# MCED_schematic.net
KiCad netlist of a schematic drawn in Altium Designer
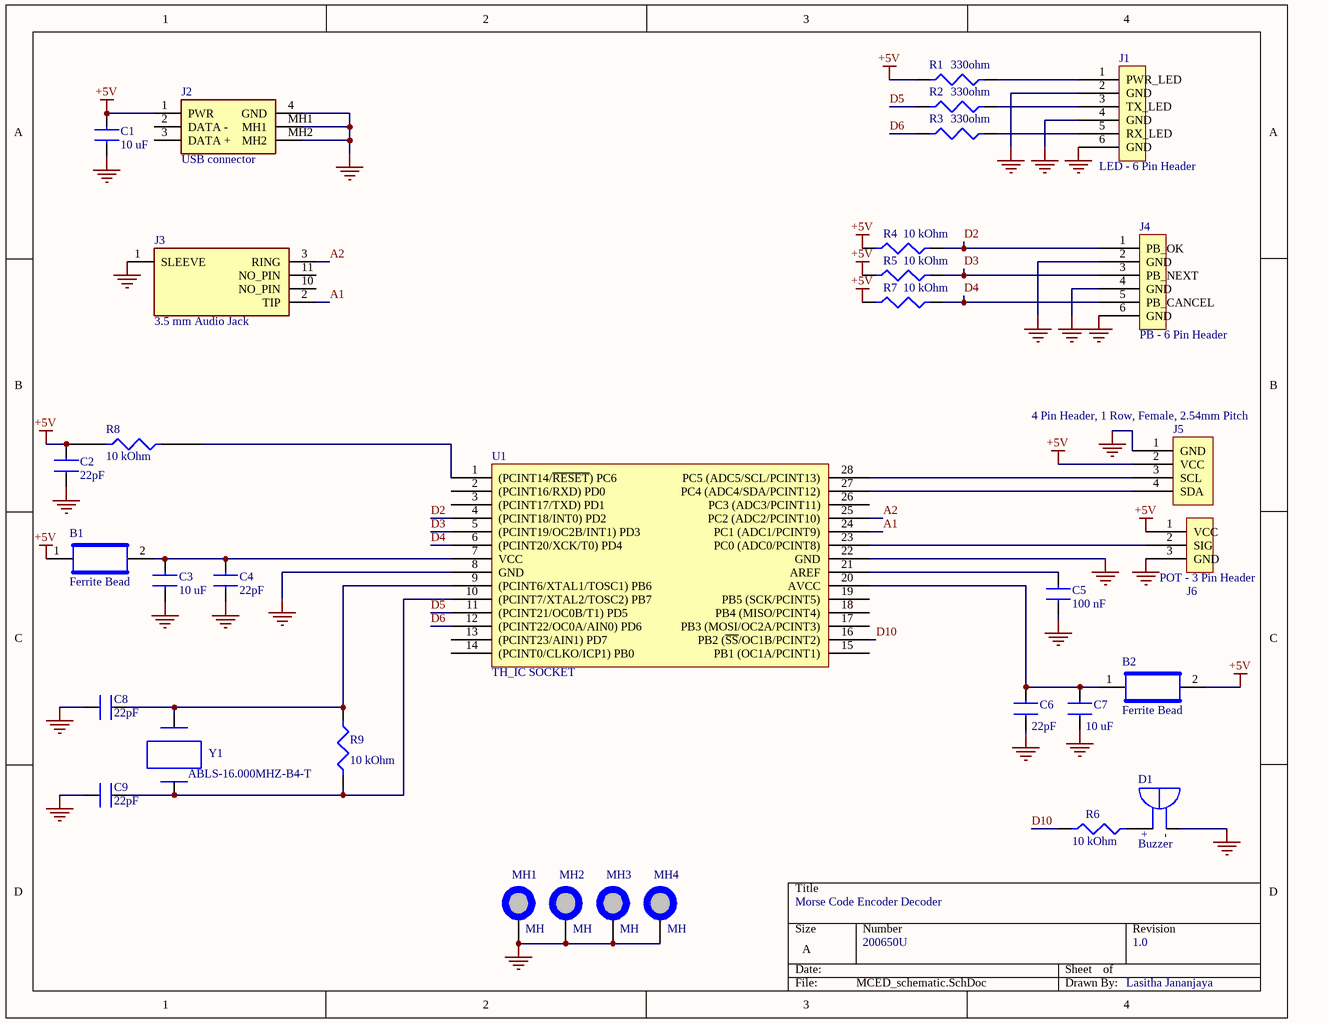
[diagram p0: MCED_schematic.SchDoc]

(export (version "E")
  (design (tool "Eeschema 10.0.6"))
  (components
    (comp (ref "B1")
      (value "Ferrite Bead")
      (footprint "FERRITE BEAD C2012X105N")
      (description "Ferrite Bead, 1 Function(s), 2A")
      (fields
        (field (name "MANUFACTURER") "TDK")
        (field (name "MANUFACTURER PART NUMBER") "MPZ2012S601AT000")
      )
      (libsource (lib "MCED_Schlib") (part "MPZ2012S601AT000"))
    )
    (comp (ref "B2")
      (value "Ferrite Bead")
      (footprint "FERRITE BEAD C2012X105N")
      (description "Ferrite Bead, 1 Function(s), 2A")
      (fields
        (field (name "MANUFACTURER") "TDK")
        (field (name "MANUFACTURER PART NUMBER") "MPZ2012S601AT000")
      )
      (libsource (lib "MCED_Schlib") (part "MPZ2012S601AT000"))
    )
    (comp (ref "C1")
      (value "10 uF")
      (footprint "C0805")
      (fields
        (field (name "MANUFACTURER") "Samsung")
        (field (name "MANUFACTURER PART NUMBER") "CL21A106KBYQNNE")
      )
      (libsource (lib "MCED_Schlib") (part "CL21A106KBYQNNE"))
    )
    (comp (ref "C2")
      (value "22pF")
      (footprint "C0805")
      (fields
        (field (name "MANUFACTURER") "Vishay Vitramon")
        (field (name "MANUFACTURER PART NUMBER") "VJ0805A220GXACW1BC")
      )
      (libsource (lib "MCED_Schlib") (part "VJ0805A220GXACW1BC"))
    )
    (comp (ref "C3")
      (value "10 uF")
      (footprint "C0805")
      (fields
        (field (name "MANUFACTURER") "Samsung")
        (field (name "MANUFACTURER PART NUMBER") "CL21A106KBYQNNE")
      )
      (libsource (lib "MCED_Schlib") (part "CL21A106KBYQNNE"))
    )
    (comp (ref "C4")
      (value "22pF")
      (footprint "C0805")
      (fields
        (field (name "MANUFACTURER") "Vishay Vitramon")
        (field (name "MANUFACTURER PART NUMBER") "VJ0805A220GXACW1BC")
      )
      (libsource (lib "MCED_Schlib") (part "VJ0805A220GXACW1BC"))
    )
    (comp (ref "C5")
      (value "100 nF")
      (footprint "C0805")
      (fields
        (field (name "MANUFACTURER") "Samsung")
        (field (name "MANUFACTURER PART NUMBER") "CL21A106KBYQNNE")
      )
      (libsource (lib "MCED_Schlib") (part "CL21A106KBYQNNE"))
    )
    (comp (ref "C6")
      (value "22pF")
      (footprint "C0805")
      (fields
        (field (name "MANUFACTURER") "Vishay Vitramon")
        (field (name "MANUFACTURER PART NUMBER") "VJ0805A220GXACW1BC")
      )
      (libsource (lib "MCED_Schlib") (part "VJ0805A220GXACW1BC"))
    )
    (comp (ref "C7")
      (value "10 uF")
      (footprint "C0805")
      (fields
        (field (name "MANUFACTURER") "Samsung")
        (field (name "MANUFACTURER PART NUMBER") "CL21A106KBYQNNE")
      )
      (libsource (lib "MCED_Schlib") (part "CL21A106KBYQNNE"))
    )
    (comp (ref "C8")
      (value "22pF")
      (footprint "C0805")
      (fields
        (field (name "MANUFACTURER") "Vishay Vitramon")
        (field (name "MANUFACTURER PART NUMBER") "VJ0805A220GXACW1BC")
      )
      (libsource (lib "MCED_Schlib") (part "VJ0805A220GXACW1BC"))
    )
    (comp (ref "C9")
      (value "22pF")
      (footprint "C0805")
      (fields
        (field (name "MANUFACTURER") "Vishay Vitramon")
        (field (name "MANUFACTURER PART NUMBER") "VJ0805A220GXACW1BC")
      )
      (libsource (lib "MCED_Schlib") (part "VJ0805A220GXACW1BC"))
    )
    (comp (ref "D1")
      (value "Buzzer")
      (footprint "Buzzer")
      (fields (field (name "MF") "Kingstate") (field (name "MP") "KXG1201C"))
      (libsource (lib "MCED_Schlib") (part "KXG1201C"))
    )
    (comp (ref "J1")
      (value "LED - 6 Pin Header")
      (footprint "6 PIN HEADER")
      (description "6 Pin Header Board Connector")
      (fields (field (name "MANUFACTURER") "3M") (field (name "MANUFACTURER PART NUMBER") "929850-01-06-RB"))
      (libsource (lib "MCED_Schlib") (part "929850-01-06-RB"))
    )
    (comp (ref "J2")
      (value "USB connector")
      (footprint "USB 2.0 type B 617291011BLF")
      (description "USB 2.0 connector, Type B, Receptacle, Through Hole, 30u GXT Contact, 4 Pins, 1.57mm PCB")
      (fields
        (field (name "MANUFACTURER") "Amphenol ICC / FCI")
        (field (name "MANUFACTURER PART NUMBER") "61729-1011BLF")
      )
      (libsource (lib "MCED_Schlib") (part "61729-1011BLF"))
    )
    (comp (ref "J3")
      (value "3.5 mm Audio Jack")
      (footprint "Audio Jack SJ13523N")
      (description "3.5 mm Audio Jack, Female, 3 Pole(s), Solder Terminal, Jack")
      (fields
        (field (name "MANUFACTURER") "CUI Devices")
        (field (name "MANUFACTURER PART NUMBER") "SJ1-3523N")
      )
      (libsource (lib "MCED_Schlib") (part "SJ1-3523N"))
    )
    (comp (ref "J4")
      (value "PB - 6 Pin Header")
      (footprint "6 PIN HEADER")
      (description "6 Pin Header Board Connector")
      (fields (field (name "MANUFACTURER") "3M") (field (name "MANUFACTURER PART NUMBER") "929850-01-06-RB"))
      (libsource (lib "MCED_Schlib") (part "929850-01-06-RB"))
    )
    (comp (ref "J5")
      (value "4 Pin Header, 1 Row, Female, 2.54mm Pitch")
      (footprint "4 Pin Header")
      (fields (field (name "MANUFACTURER") "Harwin") (field (name "MANUFACTURER PART NUMBER") "M20-7820446"))
      (libsource (lib "MCED_Schlib") (part "M20-7820446"))
    )
    (comp (ref "J6")
      (value "POT - 3 Pin Header")
      (footprint "3 PIN HEADER")
      (description "3 Pin Header Board Connector, 3 Contact(s), 1 Row(s), Female, Straight, Solder Terminal, Socket")
      (fields (field (name "MANUFACTURER") "3M") (field (name "MANUFACTURER PART NUMBER") "929850-01-03-RA"))
      (libsource (lib "MCED_Schlib") (part "929850-01-03-RA"))
    )
    (comp (ref "MH1")
      (value "MH")
      (footprint "Mounting Hole")
      (libsource (lib "MCED_Schlib") (part "Mounting Hole"))
    )
    (comp (ref "MH2")
      (value "MH")
      (footprint "Mounting Hole")
      (libsource (lib "MCED_Schlib") (part "Mounting Hole"))
    )
    (comp (ref "MH3")
      (value "MH")
      (footprint "Mounting Hole")
      (libsource (lib "MCED_Schlib") (part "Mounting Hole"))
    )
    (comp (ref "MH4")
      (value "MH")
      (footprint "Mounting Hole")
      (libsource (lib "MCED_Schlib") (part "Mounting Hole"))
    )
    (comp (ref "R1")
      (value "330ohm")
      (footprint "300Ohm RESC2012X60N")
      (fields
        (field (name "MANUFACTURER") "Vishay")
        (field (name "MANUFACTURER PART NUMBER") "CRCW0805330RFKEA")
        (field (name "TOLERANCE") "1%")
      )
      (libsource (lib "MCED_Schlib") (part "CRCW0805330RFKEA"))
    )
    (comp (ref "R2")
      (value "330ohm")
      (footprint "300Ohm RESC2012X60N")
      (fields
        (field (name "MANUFACTURER") "Vishay")
        (field (name "MANUFACTURER PART NUMBER") "CRCW0805330RFKEA")
        (field (name "TOLERANCE") "1%")
      )
      (libsource (lib "MCED_Schlib") (part "CRCW0805330RFKEA"))
    )
    (comp (ref "R3")
      (value "330ohm")
      (footprint "300Ohm RESC2012X60N")
      (fields
        (field (name "MANUFACTURER") "Vishay")
        (field (name "MANUFACTURER PART NUMBER") "CRCW0805330RFKEA")
        (field (name "TOLERANCE") "1%")
      )
      (libsource (lib "MCED_Schlib") (part "CRCW0805330RFKEA"))
    )
    (comp (ref "R4")
      (value "10 kOhm")
      (footprint "10K")
      (description "10 kOhm, Fixed Resistor, Thin Film, 0.2W, 10000ohm, 150V, 0.5% +/-Tol, -25,25ppm/Cel, 0805")
      (fields
        (field (name "MANUFACTURER") "Vishay Beyschlag")
        (field (name "MANUFACTURER PART NUMBER") "MCU0805MD1002DP500")
      )
      (libsource (lib "MCED_Schlib") (part "MCU0805MD1002DP500"))
    )
    (comp (ref "R5")
      (value "10 kOhm")
      (footprint "10K")
      (description "10 kOhm, Fixed Resistor, Thin Film, 0.2W, 10000ohm, 150V, 0.5% +/-Tol, -25,25ppm/Cel, 0805")
      (fields
        (field (name "MANUFACTURER") "Vishay Beyschlag")
        (field (name "MANUFACTURER PART NUMBER") "MCU0805MD1002DP500")
      )
      (libsource (lib "MCED_Schlib") (part "MCU0805MD1002DP500"))
    )
    (comp (ref "R6")
      (value "10 kOhm")
      (footprint "10K")
      (description "10 kOhm, Fixed Resistor, Thin Film, 0.2W, 10000ohm, 150V, 0.5% +/-Tol, -25,25ppm/Cel, 0805")
      (fields
        (field (name "MANUFACTURER") "Vishay Beyschlag")
        (field (name "MANUFACTURER PART NUMBER") "MCU0805MD1002DP500")
      )
      (libsource (lib "MCED_Schlib") (part "MCU0805MD1002DP500"))
    )
    (comp (ref "R7")
      (value "10 kOhm")
      (footprint "10K")
      (description "10 kOhm, Fixed Resistor, Thin Film, 0.2W, 10000ohm, 150V, 0.5% +/-Tol, -25,25ppm/Cel, 0805")
      (fields
        (field (name "MANUFACTURER") "Vishay Beyschlag")
        (field (name "MANUFACTURER PART NUMBER") "MCU0805MD1002DP500")
      )
      (libsource (lib "MCED_Schlib") (part "MCU0805MD1002DP500"))
    )
    (comp (ref "R8")
      (value "10 kOhm")
      (footprint "10K")
      (description "10 kOhm, Fixed Resistor, Thin Film, 0.2W, 10000ohm, 150V, 0.5% +/-Tol, -25,25ppm/Cel, 0805")
      (fields
        (field (name "MANUFACTURER") "Vishay Beyschlag")
        (field (name "MANUFACTURER PART NUMBER") "MCU0805MD1002DP500")
      )
      (libsource (lib "") (part "MCU0805MD1002DP500_1"))
    )
    (comp (ref "R9")
      (value "10 kOhm")
      (footprint "10K")
      (description "10 kOhm, Fixed Resistor, Thin Film, 0.2W, 10000ohm, 150V, 0.5% +/-Tol, -25,25ppm/Cel, 0805")
      (fields
        (field (name "MANUFACTURER") "Vishay Beyschlag")
        (field (name "MANUFACTURER PART NUMBER") "MCU0805MD1002DP500")
      )
      (libsource (lib "MCED_Schlib") (part "MCU0805MD1002DP500"))
    )
    (comp (ref "U1")
      (value "TH_IC SOCKET")
      (footprint "28dip_through_hole_ic_socket")
      (description "Through Hole IC Sockets 28P / .300\"")
      (fields
        (field (name "MANUFACTURER") "Adam Equipment")
        (field (name "MANUFACTURER PART NUMBER") "ICS-328-T")
      )
      (libsource (lib "MCED_Schlib") (part "ICS-328-T"))
    )
    (comp (ref "Y1")
      (value "ABLS-16.000MHZ-B4-T")
      (footprint "ABLS-16.000MHZ-B4-T_CRYSTAL")
      (description "16MHz ±30ppm 晶体 18pF 40 欧姆 -20°C ~ 70°C  表面贴装 HC49/US")
      (fields (field (name "MANUFACTURER") "Abracon"))
      (libsource (lib "MCED_Schlib") (part "ABLS-16.000MHZ-B4-T"))
    )
  )
  (nets
    (net (code "1") (name "+5V") (class "Default")
      (node (ref "B1") (pin "1") (pinfunction "1_1") (pintype "passive"))
      (node (ref "B2") (pin "2") (pinfunction "2_2") (pintype "passive"))
      (node (ref "C1") (pin "2") (pinfunction "2_2") (pintype "passive"))
      (node (ref "C2") (pin "2") (pinfunction "2_2") (pintype "passive"))
      (node (ref "J2") (pin "1") (pinfunction "PWR_1") (pintype "passive"))
      (node (ref "J5") (pin "2") (pinfunction "VCC_2") (pintype "passive"))
      (node (ref "J6") (pin "1") (pinfunction "VCC_1") (pintype "passive"))
      (node (ref "R1") (pin "1") (pinfunction "1_1") (pintype "passive"))
      (node (ref "R4") (pin "2") (pinfunction "2_2") (pintype "passive"))
      (node (ref "R5") (pin "2") (pinfunction "2_2") (pintype "passive"))
      (node (ref "R7") (pin "2") (pinfunction "2_2") (pintype "passive"))
      (node (ref "R8") (pin "2") (pinfunction "2_2") (pintype "passive"))
    )
    (net (code "2") (name "/A1") (class "Default")
      (node (ref "J3") (pin "2") (pinfunction "TIP_2") (pintype "passive"))
      (node (ref "U1") (pin "24") (pinfunction "PC1_(ADC1/PCINT9)_24") (pintype "passive"))
    )
    (net (code "3") (name "/A2") (class "Default")
      (node (ref "J3") (pin "3") (pinfunction "RING_3") (pintype "passive"))
      (node (ref "U1") (pin "25") (pinfunction "PC2_(ADC2/PCINT10)_25") (pintype "passive"))
    )
    (net (code "4") (name "/D2") (class "Default")
      (node (ref "J4") (pin "1") (pinfunction "PWR_LED_1") (pintype "passive"))
      (node (ref "R4") (pin "1") (pinfunction "1_1") (pintype "passive"))
      (node (ref "U1") (pin "4") (pinfunction "(PCINT18/INT0)_PD2_4") (pintype "passive"))
    )
    (net (code "5") (name "/D3") (class "Default")
      (node (ref "J4") (pin "3") (pinfunction "TX_LED_3") (pintype "passive"))
      (node (ref "R5") (pin "1") (pinfunction "1_1") (pintype "passive"))
      (node (ref "U1") (pin "5") (pinfunction "(PCINT19/OC2B/INT1)_PD3_5") (pintype "passive"))
    )
    (net (code "6") (name "/D4") (class "Default")
      (node (ref "J4") (pin "5") (pinfunction "RX_LED_5") (pintype "passive"))
      (node (ref "R7") (pin "1") (pinfunction "1_1") (pintype "passive"))
      (node (ref "U1") (pin "6") (pinfunction "(PCINT20/XCK/T0)_PD4_6") (pintype "passive"))
    )
    (net (code "7") (name "/D5") (class "Default")
      (node (ref "R2") (pin "1") (pinfunction "1_1") (pintype "passive"))
      (node (ref "U1") (pin "11") (pinfunction "(PCINT21/OC0B/T1)_PD5_11") (pintype "passive"))
    )
    (net (code "8") (name "/D6") (class "Default")
      (node (ref "R3") (pin "1") (pinfunction "1_1") (pintype "passive"))
      (node (ref "U1") (pin "12") (pinfunction "(PCINT22/OC0A/AIN0)_PD6_12") (pintype "passive"))
    )
    (net (code "9") (name "/D10") (class "Default")
      (node (ref "R6") (pin "2") (pinfunction "2_2") (pintype "passive"))
      (node (ref "U1") (pin "16") (pinfunction "PB2_(~{SS}/OC1B/PCINT2)_16") (pintype "passive"))
    )
    (net (code "10") (name "GND") (class "Default")
      (node (ref "C1") (pin "1") (pinfunction "1_1") (pintype "passive"))
      (node (ref "C2") (pin "1") (pinfunction "1_1") (pintype "passive"))
      (node (ref "C3") (pin "1") (pinfunction "1_1") (pintype "passive"))
      (node (ref "C4") (pin "1") (pinfunction "1_1") (pintype "passive"))
      (node (ref "C5") (pin "1") (pinfunction "1_1") (pintype "passive"))
      (node (ref "C6") (pin "1") (pinfunction "1_1") (pintype "passive"))
      (node (ref "C7") (pin "1") (pinfunction "1_1") (pintype "passive"))
      (node (ref "C8") (pin "2") (pinfunction "2_2") (pintype "passive"))
      (node (ref "C9") (pin "2") (pinfunction "2_2") (pintype "passive"))
      (node (ref "D1") (pin "N") (pinfunction "NEG_N") (pintype "passive"))
      (node (ref "J1") (pin "2") (pinfunction "GND_2") (pintype "passive"))
      (node (ref "J1") (pin "4") (pinfunction "GND_4") (pintype "passive"))
      (node (ref "J1") (pin "6") (pinfunction "GND_6") (pintype "passive"))
      (node (ref "J2") (pin "4") (pinfunction "GND_4") (pintype "passive"))
      (node (ref "J2") (pin "MH1") (pinfunction "MH1_MH1") (pintype "passive"))
      (node (ref "J2") (pin "MH2") (pinfunction "MH2_MH2") (pintype "passive"))
      (node (ref "J3") (pin "1") (pinfunction "SLEEVE_1") (pintype "passive"))
      (node (ref "J4") (pin "2") (pinfunction "GND_2") (pintype "passive"))
      (node (ref "J4") (pin "4") (pinfunction "GND_4") (pintype "passive"))
      (node (ref "J4") (pin "6") (pinfunction "GND_6") (pintype "passive"))
      (node (ref "J5") (pin "1") (pinfunction "GND_1") (pintype "passive"))
      (node (ref "J6") (pin "3") (pinfunction "GND_3") (pintype "passive"))
      (node (ref "MH1") (pin "1") (pinfunction "1_1") (pintype "passive"))
      (node (ref "MH2") (pin "1") (pinfunction "1_1") (pintype "passive"))
      (node (ref "MH3") (pin "1") (pinfunction "1_1") (pintype "passive"))
      (node (ref "MH4") (pin "1") (pinfunction "1_1") (pintype "passive"))
      (node (ref "U1") (pin "22") (pinfunction "GND_22") (pintype "passive"))
      (node (ref "U1") (pin "8") (pinfunction "GND_8") (pintype "passive"))
    )
    (net (code "11") (name "Net-(D1-POS)") (class "Default")
      (node (ref "D1") (pin "P") (pinfunction "POS_P") (pintype "passive"))
      (node (ref "R6") (pin "1") (pinfunction "1_1") (pintype "passive"))
    )
    (net (code "12") (name "Net-(J1-PWR_LED)") (class "Default")
      (node (ref "J1") (pin "1") (pinfunction "PWR_LED_1") (pintype "passive"))
      (node (ref "R1") (pin "2") (pinfunction "2_2") (pintype "passive"))
    )
    (net (code "13") (name "Net-(J1-RX_LED)") (class "Default")
      (node (ref "J1") (pin "5") (pinfunction "RX_LED_5") (pintype "passive"))
      (node (ref "R3") (pin "2") (pinfunction "2_2") (pintype "passive"))
    )
    (net (code "14") (name "Net-(J1-TX_LED)") (class "Default")
      (node (ref "J1") (pin "3") (pinfunction "TX_LED_3") (pintype "passive"))
      (node (ref "R2") (pin "2") (pinfunction "2_2") (pintype "passive"))
    )
    (net (code "15") (name "Net-(J5-SCL)") (class "Default")
      (node (ref "J5") (pin "3") (pinfunction "SCL_3") (pintype "passive"))
      (node (ref "U1") (pin "28") (pinfunction "PC5_(ADC5/SCL/PCINT13)_28") (pintype "passive"))
    )
    (net (code "16") (name "Net-(J5-SDA)") (class "Default")
      (node (ref "J5") (pin "4") (pinfunction "SDA_4") (pintype "passive"))
      (node (ref "U1") (pin "27") (pinfunction "PC4_(ADC4/SDA/PCINT12)_27") (pintype "passive"))
    )
    (net (code "17") (name "Net-(J6-SIG)") (class "Default")
      (node (ref "J6") (pin "2") (pinfunction "SIG_2") (pintype "passive"))
      (node (ref "U1") (pin "23") (pinfunction "PC0_(ADC0/PCINT8)_23") (pintype "passive"))
    )
    (net (code "18") (name "Net-(U1-(PCINT6{slash}XTAL1{slash}TOSC1)_PB6)") (class "Default")
      (node (ref "C8") (pin "1") (pinfunction "1_1") (pintype "passive"))
      (node (ref "R9") (pin "2") (pinfunction "2_2") (pintype "passive"))
      (node (ref "U1") (pin "9") (pinfunction "(PCINT6/XTAL1/TOSC1)_PB6_9") (pintype "passive"))
      (node (ref "Y1") (pin "2") (pinfunction "2_2") (pintype "passive"))
    )
    (net (code "19") (name "Net-(U1-(PCINT7{slash}XTAL2{slash}TOSC2)_PB7)") (class "Default")
      (node (ref "C9") (pin "1") (pinfunction "1_1") (pintype "passive"))
      (node (ref "R9") (pin "1") (pinfunction "1_1") (pintype "passive"))
      (node (ref "U1") (pin "10") (pinfunction "(PCINT7/XTAL2/TOSC2)_PB7_10") (pintype "passive"))
      (node (ref "Y1") (pin "1") (pinfunction "1_1") (pintype "passive"))
    )
    (net (code "20") (name "Net-(U1-(PCINT14{slash}~{RESET})_PC6)") (class "Default")
      (node (ref "R8") (pin "1") (pinfunction "1_1") (pintype "passive"))
      (node (ref "U1") (pin "1") (pinfunction "(PCINT14/~{RESET})_PC6_1") (pintype "passive"))
    )
    (net (code "21") (name "Net-(U1-AREF)") (class "Default")
      (node (ref "C5") (pin "2") (pinfunction "2_2") (pintype "passive"))
      (node (ref "U1") (pin "21") (pinfunction "AREF_21") (pintype "passive"))
    )
    (net (code "22") (name "Net-(U1-AVCC)") (class "Default")
      (node (ref "B2") (pin "1") (pinfunction "1_1") (pintype "passive"))
      (node (ref "C6") (pin "2") (pinfunction "2_2") (pintype "passive"))
      (node (ref "C7") (pin "2") (pinfunction "2_2") (pintype "passive"))
      (node (ref "U1") (pin "20") (pinfunction "AVCC_20") (pintype "passive"))
    )
    (net (code "23") (name "Net-(U1-VCC)") (class "Default")
      (node (ref "B1") (pin "2") (pinfunction "2_2") (pintype "passive"))
      (node (ref "C3") (pin "2") (pinfunction "2_2") (pintype "passive"))
      (node (ref "C4") (pin "2") (pinfunction "2_2") (pintype "passive"))
      (node (ref "U1") (pin "7") (pinfunction "VCC_7") (pintype "passive"))
    )
    (net (code "24") (name "unconnected-(J2-DATA_+-Pad3)") (class "Default")
      (node (ref "J2") (pin "3") (pinfunction "DATA_+_3") (pintype "passive"))
    )
    (net (code "25") (name "unconnected-(J2-DATA_--Pad2)") (class "Default")
      (node (ref "J2") (pin "2") (pinfunction "DATA_-_2") (pintype "passive"))
    )
    (net (code "26") (name "unconnected-(J3-NO_PIN-Pad10)") (class "Default")
      (node (ref "J3") (pin "10") (pinfunction "NO_PIN_10") (pintype "passive"))
    )
    (net (code "27") (name "unconnected-(J3-NO_PIN-Pad11)") (class "Default")
      (node (ref "J3") (pin "11") (pinfunction "NO_PIN_11") (pintype "passive"))
    )
    (net (code "28") (name "unconnected-(U1-(PCINT0{slash}CLKO{slash}ICP1)_PB0-Pad14)") (class "Default")
      (node (ref "U1") (pin "14") (pinfunction "(PCINT0/CLKO/ICP1)_PB0_14") (pintype "passive"))
    )
    (net (code "29") (name "unconnected-(U1-(PCINT16{slash}RXD)_PD0-Pad2)") (class "Default")
      (node (ref "U1") (pin "2") (pinfunction "(PCINT16/RXD)_PD0_2") (pintype "passive"))
    )
    (net (code "30") (name "unconnected-(U1-(PCINT17{slash}TXD)_PD1-Pad3)") (class "Default")
      (node (ref "U1") (pin "3") (pinfunction "(PCINT17/TXD)_PD1_3") (pintype "passive"))
    )
    (net (code "31") (name "unconnected-(U1-(PCINT23{slash}AIN1)_PD7-Pad13)") (class "Default")
      (node (ref "U1") (pin "13") (pinfunction "(PCINT23/AIN1)_PD7_13") (pintype "passive"))
    )
    (net (code "32") (name "unconnected-(U1-PB1_(OC1A{slash}PCINT1)-Pad15)") (class "Default")
      (node (ref "U1") (pin "15") (pinfunction "PB1_(OC1A/PCINT1)_15") (pintype "passive"))
    )
    (net (code "33") (name "unconnected-(U1-PB3_(MOSI{slash}OC2A{slash}PCINT3)-Pad17)") (class "Default")
      (node (ref "U1") (pin "17") (pinfunction "PB3_(MOSI/OC2A/PCINT3)_17") (pintype "passive"))
    )
    (net (code "34") (name "unconnected-(U1-PB4_(MISO{slash}PCINT4)-Pad18)") (class "Default")
      (node (ref "U1") (pin "18") (pinfunction "PB4_(MISO/PCINT4)_18") (pintype "passive"))
    )
    (net (code "35") (name "unconnected-(U1-PB5_(SCK{slash}PCINT5)-Pad19)") (class "Default")
      (node (ref "U1") (pin "19") (pinfunction "PB5_(SCK/PCINT5)_19") (pintype "passive"))
    )
    (net (code "36") (name "unconnected-(U1-PC3_(ADC3{slash}PCINT11)-Pad26)") (class "Default")
      (node (ref "U1") (pin "26") (pinfunction "PC3_(ADC3/PCINT11)_26") (pintype "passive"))
    )
  )
)
